# support.net
KiCad netlist of a schematic drawn in Altium Designer
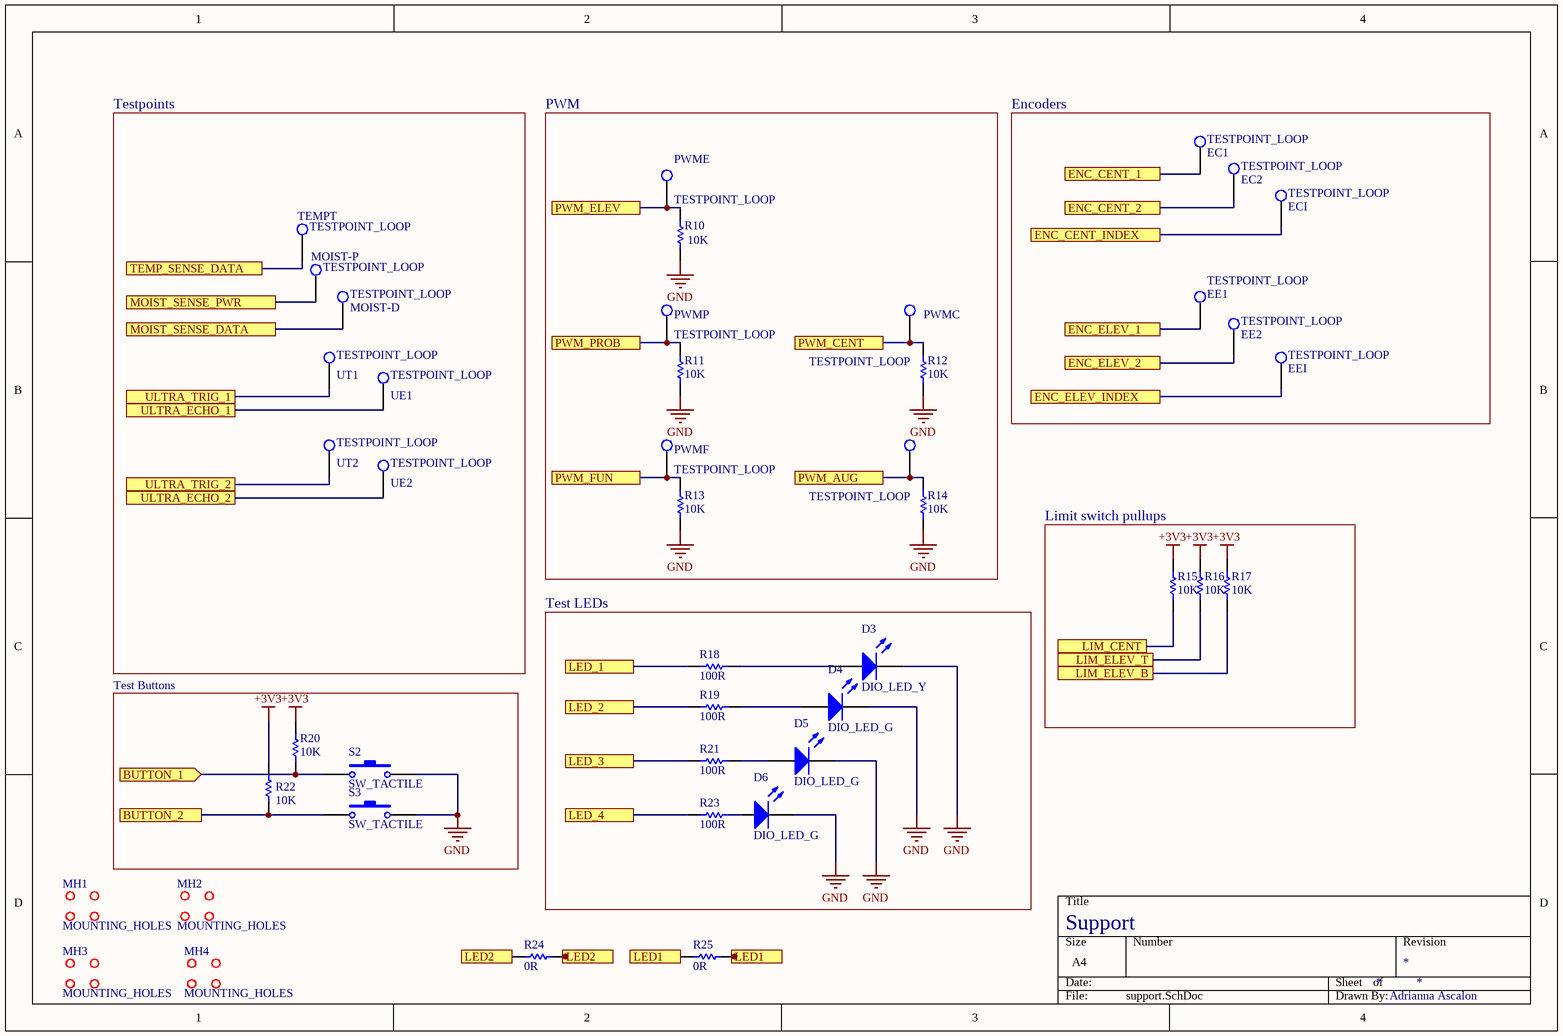
[diagram p0: support.SchDoc]

(export (version "E")
  (design (tool "Eeschema 10.0.6"))
  (components
    (comp (ref "D3")
      (value "DIO_LED_Y")
      (footprint "LED_0805_LINE")
      (description "LED YELLOW DIFFUSED 0805 SMD")
      (fields (field (name "MANUFACTURER") "OSRAM") (field (name "MPN") "LY R976-PS-36"))
      (libsource (lib "UWRT_Schematic_Library_2019") (part "DIO_LED_Y"))
    )
    (comp (ref "D4")
      (value "DIO_LED_G")
      (footprint "LED_0805_LINE")
      (description "LED GREEN DIFFUSED 0805 SMD")
      (fields (field (name "MANUFACTURER") "OSRAM") (field (name "MPN") "LG R971-KN-1"))
      (libsource (lib "UWRT_Schematic_Library_2019") (part "DIO_LED_G"))
    )
    (comp (ref "D5")
      (value "DIO_LED_G")
      (footprint "LED_0805_LINE")
      (description "LED GREEN DIFFUSED 0805 SMD")
      (fields (field (name "MANUFACTURER") "OSRAM") (field (name "MPN") "LG R971-KN-1"))
      (libsource (lib "UWRT_Schematic_Library_2019") (part "DIO_LED_G"))
    )
    (comp (ref "D6")
      (value "DIO_LED_G")
      (footprint "LED_0805_LINE")
      (description "LED GREEN DIFFUSED 0805 SMD")
      (fields (field (name "MANUFACTURER") "OSRAM") (field (name "MPN") "LG R971-KN-1"))
      (libsource (lib "UWRT_Schematic_Library_2019") (part "DIO_LED_G"))
    )
    (comp (ref "EC1")
      (value "TESTPOINT_LOOP")
      (footprint "TESTPOINT_LOOP")
      (libsource (lib "UWRT_Schematic_Library_2019") (part "TESTPOINT_LOOP"))
    )
    (comp (ref "EC2")
      (value "TESTPOINT_LOOP")
      (footprint "TESTPOINT_LOOP")
      (libsource (lib "UWRT_Schematic_Library_2019") (part "TESTPOINT_LOOP"))
    )
    (comp (ref "ECI")
      (value "TESTPOINT_LOOP")
      (footprint "TESTPOINT_LOOP")
      (libsource (lib "UWRT_Schematic_Library_2019") (part "TESTPOINT_LOOP"))
    )
    (comp (ref "EE1")
      (value "TESTPOINT_LOOP")
      (footprint "TESTPOINT_LOOP")
      (libsource (lib "UWRT_Schematic_Library_2019") (part "TESTPOINT_LOOP"))
    )
    (comp (ref "EE2")
      (value "TESTPOINT_LOOP")
      (footprint "TESTPOINT_LOOP")
      (libsource (lib "UWRT_Schematic_Library_2019") (part "TESTPOINT_LOOP"))
    )
    (comp (ref "EEI")
      (value "TESTPOINT_LOOP")
      (footprint "TESTPOINT_LOOP")
      (libsource (lib "UWRT_Schematic_Library_2019") (part "TESTPOINT_LOOP"))
    )
    (comp (ref "MH1")
      (value "MOUNTING_HOLES")
      (footprint "MOUNTING_HOLE")
      (description "6cm x 6cm")
      (libsource (lib "UWRT_Schematic_Library_2019") (part "MOUNTING_HOLES"))
    )
    (comp (ref "MH2")
      (value "MOUNTING_HOLES")
      (footprint "MOUNTING_HOLE")
      (description "6cm x 6cm")
      (libsource (lib "UWRT_Schematic_Library_2019") (part "MOUNTING_HOLES"))
    )
    (comp (ref "MH3")
      (value "MOUNTING_HOLES")
      (footprint "MOUNTING_HOLE")
      (description "6cm x 6cm")
      (libsource (lib "UWRT_Schematic_Library_2019") (part "MOUNTING_HOLES"))
    )
    (comp (ref "MH4")
      (value "MOUNTING_HOLES")
      (footprint "MOUNTING_HOLE")
      (description "6cm x 6cm")
      (libsource (lib "UWRT_Schematic_Library_2019") (part "MOUNTING_HOLES"))
    )
    (comp (ref "MOIST-D")
      (value "TESTPOINT_LOOP")
      (footprint "TESTPOINT_LOOP")
      (libsource (lib "UWRT_Schematic_Library_2019") (part "TESTPOINT_LOOP"))
    )
    (comp (ref "MOIST-P")
      (value "TESTPOINT_LOOP")
      (footprint "TESTPOINT_LOOP")
      (libsource (lib "UWRT_Schematic_Library_2019") (part "TESTPOINT_LOOP"))
    )
    (comp (ref "PWMA")
      (value "TESTPOINT_LOOP")
      (footprint "TESTPOINT_LOOP")
      (libsource (lib "UWRT_Schematic_Library_2019") (part "TESTPOINT_LOOP"))
    )
    (comp (ref "PWMC")
      (value "TESTPOINT_LOOP")
      (footprint "TESTPOINT_LOOP")
      (libsource (lib "UWRT_Schematic_Library_2019") (part "TESTPOINT_LOOP"))
    )
    (comp (ref "PWME")
      (value "TESTPOINT_LOOP")
      (footprint "TESTPOINT_LOOP")
      (libsource (lib "UWRT_Schematic_Library_2019") (part "TESTPOINT_LOOP"))
    )
    (comp (ref "PWMF")
      (value "TESTPOINT_LOOP")
      (footprint "TESTPOINT_LOOP")
      (libsource (lib "UWRT_Schematic_Library_2019") (part "TESTPOINT_LOOP"))
    )
    (comp (ref "PWMP")
      (value "TESTPOINT_LOOP")
      (footprint "TESTPOINT_LOOP")
      (libsource (lib "UWRT_Schematic_Library_2019") (part "TESTPOINT_LOOP"))
    )
    (comp (ref "R10")
      (value "10K")
      (footprint "RESC0603(1608)_N")
      (description "RES SMD 10K OHM 5% 1/10W 0603")
      (fields (field (name "MANUFACTURER") "Yageo") (field (name "TOLERANCE") "5%"))
      (libsource (lib "UWRT_Schematic_Library_2019") (part "RES_10K_0603"))
    )
    (comp (ref "R11")
      (value "10K")
      (footprint "RESC0603(1608)_N")
      (description "RES SMD 10K OHM 5% 1/10W 0603")
      (fields (field (name "MANUFACTURER") "Yageo") (field (name "TOLERANCE") "5%"))
      (libsource (lib "UWRT_Schematic_Library_2019") (part "RES_10K_0603"))
    )
    (comp (ref "R12")
      (value "10K")
      (footprint "RESC0603(1608)_N")
      (description "RES SMD 10K OHM 5% 1/10W 0603")
      (fields (field (name "MANUFACTURER") "Yageo") (field (name "TOLERANCE") "5%"))
      (libsource (lib "UWRT_Schematic_Library_2019") (part "RES_10K_0603"))
    )
    (comp (ref "R13")
      (value "10K")
      (footprint "RESC0603(1608)_N")
      (description "RES SMD 10K OHM 5% 1/10W 0603")
      (fields (field (name "MANUFACTURER") "Yageo") (field (name "TOLERANCE") "5%"))
      (libsource (lib "UWRT_Schematic_Library_2019") (part "RES_10K_0603"))
    )
    (comp (ref "R14")
      (value "10K")
      (footprint "RESC0603(1608)_N")
      (description "RES SMD 10K OHM 5% 1/10W 0603")
      (fields (field (name "MANUFACTURER") "Yageo") (field (name "TOLERANCE") "5%"))
      (libsource (lib "UWRT_Schematic_Library_2019") (part "RES_10K_0603"))
    )
    (comp (ref "R15")
      (value "10K")
      (footprint "RESC0603(1608)_N")
      (description "RES SMD 10K OHM 5% 1/10W 0603")
      (fields (field (name "MANUFACTURER") "Yageo") (field (name "TOLERANCE") "5%"))
      (libsource (lib "UWRT_Schematic_Library_2019") (part "RES_10K_0603"))
    )
    (comp (ref "R16")
      (value "10K")
      (footprint "RESC0603(1608)_N")
      (description "RES SMD 10K OHM 5% 1/10W 0603")
      (fields (field (name "MANUFACTURER") "Yageo") (field (name "TOLERANCE") "5%"))
      (libsource (lib "UWRT_Schematic_Library_2019") (part "RES_10K_0603"))
    )
    (comp (ref "R17")
      (value "10K")
      (footprint "RESC0603(1608)_N")
      (description "RES SMD 10K OHM 5% 1/10W 0603")
      (fields (field (name "MANUFACTURER") "Yageo") (field (name "TOLERANCE") "5%"))
      (libsource (lib "UWRT_Schematic_Library_2019") (part "RES_10K_0603"))
    )
    (comp (ref "R18")
      (value "100R")
      (footprint "RESC0603(1608)_N")
      (description "RES SMD 100 OHM 1% 1/10W 0603")
      (fields (field (name "MANUFACTURER") "Yageo") (field (name "TOLERANCE") "1%"))
      (libsource (lib "UWRT_Schematic_Library_2019") (part "RES_100R_0603"))
    )
    (comp (ref "R19")
      (value "100R")
      (footprint "RESC0603(1608)_N")
      (description "RES SMD 100 OHM 1% 1/10W 0603")
      (fields (field (name "MANUFACTURER") "Yageo") (field (name "TOLERANCE") "1%"))
      (libsource (lib "UWRT_Schematic_Library_2019") (part "RES_100R_0603"))
    )
    (comp (ref "R20")
      (value "10K")
      (footprint "RESC0603(1608)_N")
      (description "RES SMD 10K OHM 5% 1/10W 0603")
      (fields (field (name "MANUFACTURER") "Yageo") (field (name "TOLERANCE") "5%"))
      (libsource (lib "UWRT_Schematic_Library_2019") (part "RES_10K_0603"))
    )
    (comp (ref "R21")
      (value "100R")
      (footprint "RESC0603(1608)_N")
      (description "RES SMD 100 OHM 1% 1/10W 0603")
      (fields (field (name "MANUFACTURER") "Yageo") (field (name "TOLERANCE") "1%"))
      (libsource (lib "UWRT_Schematic_Library_2019") (part "RES_100R_0603"))
    )
    (comp (ref "R22")
      (value "10K")
      (footprint "RESC0603(1608)_N")
      (description "RES SMD 10K OHM 5% 1/10W 0603")
      (fields (field (name "MANUFACTURER") "Yageo") (field (name "TOLERANCE") "5%"))
      (libsource (lib "UWRT_Schematic_Library_2019") (part "RES_10K_0603"))
    )
    (comp (ref "R23")
      (value "100R")
      (footprint "RESC0603(1608)_N")
      (description "RES SMD 100 OHM 1% 1/10W 0603")
      (fields (field (name "MANUFACTURER") "Yageo") (field (name "TOLERANCE") "1%"))
      (libsource (lib "UWRT_Schematic_Library_2019") (part "RES_100R_0603"))
    )
    (comp (ref "R24")
      (value "0R")
      (footprint "RESC1206(3216)_N")
      (description "RES SMD 0 OHM JUMPER 1/10W 1206")
      (fields (field (name "MANUFACTURER") "Yageo") (field (name "MPN") "RC0603JR-070RL"))
      (libsource (lib "UWRT_Schematic_Library_2019") (part "RES_0R_1206"))
    )
    (comp (ref "R25")
      (value "0R")
      (footprint "RESC1206(3216)_N")
      (description "RES SMD 0 OHM JUMPER 1/10W 1206")
      (fields (field (name "MANUFACTURER") "Yageo") (field (name "MPN") "RC0603JR-070RL"))
      (libsource (lib "UWRT_Schematic_Library_2019") (part "RES_0R_1206"))
    )
    (comp (ref "S2")
      (value "SW_TACTILE")
      (footprint "B3U-1100P")
      (description "Tactile Switch (Grey)")
      (fields (field (name "DIGIKEY PART NUMBER") "SW1021TR-ND") (field (name "MPN") "B3U-1100P"))
      (libsource (lib "UWRT_Schematic_Library_2019") (part "SW_TACTILE"))
    )
    (comp (ref "S3")
      (value "SW_TACTILE")
      (footprint "B3U-1100P")
      (description "Tactile Switch (Grey)")
      (fields (field (name "DIGIKEY PART NUMBER") "SW1021TR-ND") (field (name "MPN") "B3U-1100P"))
      (libsource (lib "UWRT_Schematic_Library_2019") (part "SW_TACTILE"))
    )
    (comp (ref "TEMPT")
      (value "TESTPOINT_LOOP")
      (footprint "TESTPOINT_LOOP")
      (libsource (lib "UWRT_Schematic_Library_2019") (part "TESTPOINT_LOOP"))
    )
    (comp (ref "UE1")
      (value "TESTPOINT_LOOP")
      (footprint "TESTPOINT_LOOP")
      (libsource (lib "UWRT_Schematic_Library_2019") (part "TESTPOINT_LOOP"))
    )
    (comp (ref "UE2")
      (value "TESTPOINT_LOOP")
      (footprint "TESTPOINT_LOOP")
      (libsource (lib "UWRT_Schematic_Library_2019") (part "TESTPOINT_LOOP"))
    )
    (comp (ref "UT1")
      (value "TESTPOINT_LOOP")
      (footprint "TESTPOINT_LOOP")
      (libsource (lib "UWRT_Schematic_Library_2019") (part "TESTPOINT_LOOP"))
    )
    (comp (ref "UT2")
      (value "TESTPOINT_LOOP")
      (footprint "TESTPOINT_LOOP")
      (libsource (lib "UWRT_Schematic_Library_2019") (part "TESTPOINT_LOOP"))
    )
  )
  (nets
    (net (code "1") (name "+3V3") (class "Default")
      (node (ref "R15") (pin "2") (pinfunction "2_2") (pintype "passive"))
      (node (ref "R16") (pin "2") (pinfunction "2_2") (pintype "passive"))
      (node (ref "R17") (pin "2") (pinfunction "2_2") (pintype "passive"))
      (node (ref "R20") (pin "2") (pinfunction "2_2") (pintype "passive"))
      (node (ref "R22") (pin "1") (pinfunction "1_1") (pintype "passive"))
    )
    (net (code "2") (name "/BUTTON_1") (class "Default")
      (node (ref "R20") (pin "1") (pinfunction "1_1") (pintype "passive"))
      (node (ref "S2") (pin "1") (pinfunction "1_1") (pintype "passive"))
    )
    (net (code "3") (name "/BUTTON_2") (class "Default")
      (node (ref "R22") (pin "2") (pinfunction "2_2") (pintype "passive"))
      (node (ref "S3") (pin "1") (pinfunction "1_1") (pintype "passive"))
    )
    (net (code "4") (name "/ENC_CENT_1") (class "Default")
      (node (ref "EC1") (pin "1") (pinfunction "=value_1") (pintype "passive"))
    )
    (net (code "5") (name "/ENC_CENT_2") (class "Default")
      (node (ref "EC2") (pin "1") (pinfunction "=value_1") (pintype "passive"))
    )
    (net (code "6") (name "/ENC_CENT_INDEX") (class "Default")
      (node (ref "ECI") (pin "1") (pinfunction "=value_1") (pintype "passive"))
    )
    (net (code "7") (name "/ENC_ELEV_1") (class "Default")
      (node (ref "EE1") (pin "1") (pinfunction "=value_1") (pintype "passive"))
    )
    (net (code "8") (name "/ENC_ELEV_2") (class "Default")
      (node (ref "EE2") (pin "1") (pinfunction "=value_1") (pintype "passive"))
    )
    (net (code "9") (name "/ENC_ELEV_INDEX") (class "Default")
      (node (ref "EEI") (pin "1") (pinfunction "=value_1") (pintype "passive"))
    )
    (net (code "10") (name "/LED1") (class "Default")
      (node (ref "R25") (pin "1") (pinfunction "1_1") (pintype "passive"))
    )
    (net (code "11") (name "/LED2") (class "Default")
      (node (ref "R24") (pin "1") (pinfunction "1_1") (pintype "passive"))
    )
    (net (code "12") (name "/LED_1") (class "Default")
      (node (ref "R18") (pin "1") (pinfunction "1_1") (pintype "passive"))
    )
    (net (code "13") (name "/LED_2") (class "Default")
      (node (ref "R19") (pin "1") (pinfunction "1_1") (pintype "passive"))
    )
    (net (code "14") (name "/LED_3") (class "Default")
      (node (ref "R21") (pin "1") (pinfunction "1_1") (pintype "passive"))
    )
    (net (code "15") (name "/LED_4") (class "Default")
      (node (ref "R23") (pin "1") (pinfunction "1_1") (pintype "passive"))
    )
    (net (code "16") (name "/LIM_CENT") (class "Default")
      (node (ref "R15") (pin "1") (pinfunction "1_1") (pintype "passive"))
    )
    (net (code "17") (name "/LIM_ELEV_B") (class "Default")
      (node (ref "R17") (pin "1") (pinfunction "1_1") (pintype "passive"))
    )
    (net (code "18") (name "/LIM_ELEV_T") (class "Default")
      (node (ref "R16") (pin "1") (pinfunction "1_1") (pintype "passive"))
    )
    (net (code "19") (name "/MOIST_SENSE_DATA") (class "Default")
      (node (ref "MOIST-D") (pin "1") (pinfunction "=value_1") (pintype "passive"))
    )
    (net (code "20") (name "/MOIST_SENSE_PWR") (class "Default")
      (node (ref "MOIST-P") (pin "1") (pinfunction "=value_1") (pintype "passive"))
    )
    (net (code "21") (name "/PWM_AUG") (class "Default")
      (node (ref "PWMA") (pin "1") (pinfunction "=value_1") (pintype "passive"))
      (node (ref "R14") (pin "2") (pinfunction "2_2") (pintype "passive"))
    )
    (net (code "22") (name "/PWM_CENT") (class "Default")
      (node (ref "PWMC") (pin "1") (pinfunction "=value_1") (pintype "passive"))
      (node (ref "R12") (pin "2") (pinfunction "2_2") (pintype "passive"))
    )
    (net (code "23") (name "/PWM_ELEV") (class "Default")
      (node (ref "PWME") (pin "1") (pinfunction "=value_1") (pintype "passive"))
      (node (ref "R10") (pin "2") (pinfunction "2_2") (pintype "passive"))
    )
    (net (code "24") (name "/PWM_FUN") (class "Default")
      (node (ref "PWMF") (pin "1") (pinfunction "=value_1") (pintype "passive"))
      (node (ref "R13") (pin "2") (pinfunction "2_2") (pintype "passive"))
    )
    (net (code "25") (name "/PWM_PROB") (class "Default")
      (node (ref "PWMP") (pin "1") (pinfunction "=value_1") (pintype "passive"))
      (node (ref "R11") (pin "2") (pinfunction "2_2") (pintype "passive"))
    )
    (net (code "26") (name "/TEMP_SENSE_DATA") (class "Default")
      (node (ref "TEMPT") (pin "1") (pinfunction "=value_1") (pintype "passive"))
    )
    (net (code "27") (name "/ULTRA_ECHO_1") (class "Default")
      (node (ref "UE1") (pin "1") (pinfunction "=value_1") (pintype "passive"))
    )
    (net (code "28") (name "/ULTRA_ECHO_2") (class "Default")
      (node (ref "UE2") (pin "1") (pinfunction "=value_1") (pintype "passive"))
    )
    (net (code "29") (name "/ULTRA_TRIG_1") (class "Default")
      (node (ref "UT1") (pin "1") (pinfunction "=value_1") (pintype "passive"))
    )
    (net (code "30") (name "/ULTRA_TRIG_2") (class "Default")
      (node (ref "UT2") (pin "1") (pinfunction "=value_1") (pintype "passive"))
    )
    (net (code "31") (name "GND") (class "Default")
      (node (ref "D3") (pin "2") (pinfunction "K_2") (pintype "passive"))
      (node (ref "D4") (pin "2") (pinfunction "K_2") (pintype "passive"))
      (node (ref "D5") (pin "2") (pinfunction "K_2") (pintype "passive"))
      (node (ref "D6") (pin "2") (pinfunction "K_2") (pintype "passive"))
      (node (ref "R10") (pin "1") (pinfunction "1_1") (pintype "passive"))
      (node (ref "R11") (pin "1") (pinfunction "1_1") (pintype "passive"))
      (node (ref "R12") (pin "1") (pinfunction "1_1") (pintype "passive"))
      (node (ref "R13") (pin "1") (pinfunction "1_1") (pintype "passive"))
      (node (ref "R14") (pin "1") (pinfunction "1_1") (pintype "passive"))
      (node (ref "S2") (pin "2") (pinfunction "2_2") (pintype "passive"))
      (node (ref "S3") (pin "2") (pinfunction "2_2") (pintype "passive"))
    )
    (net (code "32") (name "Net-(D3-A)") (class "Default")
      (node (ref "D3") (pin "1") (pinfunction "A_1") (pintype "passive"))
      (node (ref "R18") (pin "2") (pinfunction "2_2") (pintype "passive"))
    )
    (net (code "33") (name "Net-(D4-A)") (class "Default")
      (node (ref "D4") (pin "1") (pinfunction "A_1") (pintype "passive"))
      (node (ref "R19") (pin "2") (pinfunction "2_2") (pintype "passive"))
    )
    (net (code "34") (name "Net-(D5-A)") (class "Default")
      (node (ref "D5") (pin "1") (pinfunction "A_1") (pintype "passive"))
      (node (ref "R21") (pin "2") (pinfunction "2_2") (pintype "passive"))
    )
    (net (code "35") (name "Net-(D6-A)") (class "Default")
      (node (ref "D6") (pin "1") (pinfunction "A_1") (pintype "passive"))
      (node (ref "R23") (pin "2") (pinfunction "2_2") (pintype "passive"))
    )
    (net (code "36") (name "unconnected-(R24-Pad2)") (class "Default")
      (node (ref "R24") (pin "2") (pinfunction "2_2") (pintype "passive"))
    )
    (net (code "37") (name "unconnected-(R25-Pad2)") (class "Default")
      (node (ref "R25") (pin "2") (pinfunction "2_2") (pintype "passive"))
    )
  )
)
